# smart_water_heater_v1.net
KiCad netlist of a schematic drawn in EAGLE
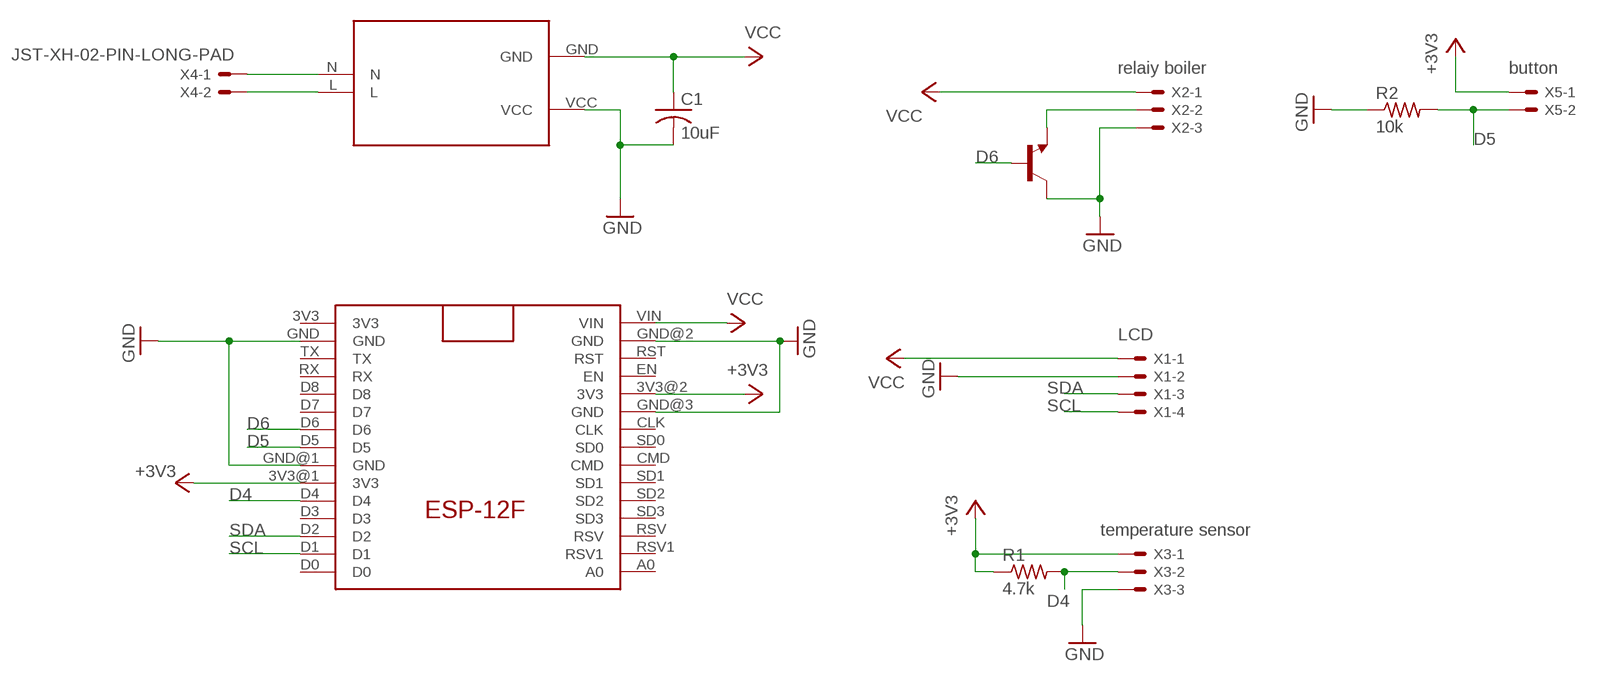
[diagram p0: schematic, sheet 1]

(export (version "E")
  (design (tool "Eeschema 10.0.6"))
  (components
    (comp (ref "C1")
      (value "10uF")
      (footprint "eagle-import:C025-025X050")
      (libsource (lib "eagle-import") (part "C-US025-025X050"))
    )
    (comp (ref "R1")
      (value "4.7k")
      (footprint "eagle-import:0204_7")
      (libsource (lib "eagle-import") (part "R-US_0204/7"))
    )
    (comp (ref "R2")
      (value "10k")
      (footprint "eagle-import:0204_7")
      (libsource (lib "eagle-import") (part "R-US_0204/7"))
    )
    (comp (ref "T1")
      (value "2N2222")
      (footprint "eagle-import:TO92-EBC-OVAL")
      (libsource (lib "eagle-import") (part "2N2222"))
    )
    (comp (ref "U$1")
      (value "ESP-12F")
      (footprint "eagle-import:ESP-12F")
      (libsource (lib "eagle-import") (part "ESP-12F"))
    )
    (comp (ref "U$2")
      (value "HLK-5M05")
      (footprint "eagle-import:CONV_HLK-5M05")
      (libsource (lib "eagle-import") (part "HLK-5M05"))
    )
    (comp (ref "X1")
      (value "22-23-2041")
      (footprint "eagle-import:22-23-2041")
      (fields (field (name "MF") "MOLEX"))
      (libsource (lib "eagle-import") (part "22-23-2041"))
    )
    (comp (ref "X2")
      (value "22-23-2031")
      (footprint "eagle-import:22-23-2031")
      (fields (field (name "MF") "MOLEX"))
      (libsource (lib "eagle-import") (part "22-23-2031"))
    )
    (comp (ref "X3")
      (value "22-23-2031")
      (footprint "eagle-import:22-23-2031")
      (fields (field (name "MF") "MOLEX"))
      (libsource (lib "eagle-import") (part "22-23-2031"))
    )
    (comp (ref "X4")
      (value "JST-XH-02-PIN-LONG-PAD")
      (footprint "eagle-import:JST-XH-02-PACKAGE-LONG-PAD")
      (libsource (lib "eagle-import") (part "JST-XH-02-PIN-LONG-PAD"))
    )
    (comp (ref "X5")
      (value "22-23-2021")
      (footprint "eagle-import:22-23-2021")
      (fields (field (name "MF") "MOLEX"))
      (libsource (lib "eagle-import") (part "22-23-2021"))
    )
  )
  (nets
    (net (code "1") (name "+3V3") (class "Default")
      (node (ref "R1") (pin "1") (pinfunction "1_1") (pintype "passive"))
      (node (ref "U$1") (pin "3V3@1") (pinfunction "3V3_3V3@1") (pintype "bidirectional"))
      (node (ref "U$1") (pin "3V3@2") (pinfunction "3V3_3V3@2") (pintype "bidirectional"))
      (node (ref "X3") (pin "1") (pinfunction "S_1") (pintype "passive"))
      (node (ref "X5") (pin "1") (pinfunction "S_1") (pintype "passive"))
    )
    (net (code "2") (name "/D4") (class "Default")
      (node (ref "R1") (pin "2") (pinfunction "2_2") (pintype "passive"))
      (node (ref "U$1") (pin "D4") (pinfunction "D4_D4") (pintype "bidirectional"))
      (node (ref "X3") (pin "2") (pinfunction "S_2") (pintype "passive"))
    )
    (net (code "3") (name "/D5") (class "Default")
      (node (ref "R2") (pin "2") (pinfunction "2_2") (pintype "passive"))
      (node (ref "U$1") (pin "D5") (pinfunction "D5_D5") (pintype "bidirectional"))
      (node (ref "X5") (pin "2") (pinfunction "S_2") (pintype "passive"))
    )
    (net (code "4") (name "/D6") (class "Default")
      (node (ref "T1") (pin "B") (pinfunction "B_B") (pintype "passive"))
      (node (ref "U$1") (pin "D6") (pinfunction "D6_D6") (pintype "bidirectional"))
    )
    (net (code "5") (name "/SCL") (class "Default")
      (node (ref "U$1") (pin "D1") (pinfunction "D1_D1") (pintype "bidirectional"))
      (node (ref "X1") (pin "4") (pinfunction "S_4") (pintype "passive"))
    )
    (net (code "6") (name "/SDA") (class "Default")
      (node (ref "U$1") (pin "D2") (pinfunction "D2_D2") (pintype "bidirectional"))
      (node (ref "X1") (pin "3") (pinfunction "S_3") (pintype "passive"))
    )
    (net (code "7") (name "GND") (class "Default")
      (node (ref "C1") (pin "2") (pinfunction "2_2") (pintype "passive"))
      (node (ref "R2") (pin "1") (pinfunction "1_1") (pintype "passive"))
      (node (ref "T1") (pin "C") (pinfunction "C_C") (pintype "passive"))
      (node (ref "U$1") (pin "GND") (pinfunction "GND_GND") (pintype "bidirectional"))
      (node (ref "U$1") (pin "GND@1") (pinfunction "GND_GND@1") (pintype "bidirectional"))
      (node (ref "U$1") (pin "GND@2") (pinfunction "GND_GND@2") (pintype "bidirectional"))
      (node (ref "U$1") (pin "GND@3") (pinfunction "GND_GND@3") (pintype "bidirectional"))
      (node (ref "U$2") (pin "VCC") (pinfunction "VCC_VCC") (pintype "bidirectional"))
      (node (ref "X1") (pin "2") (pinfunction "S_2") (pintype "passive"))
      (node (ref "X2") (pin "3") (pinfunction "S_3") (pintype "passive"))
      (node (ref "X3") (pin "3") (pinfunction "S_3") (pintype "passive"))
    )
    (net (code "8") (name "Net-(X2B-S)") (class "Default")
      (node (ref "T1") (pin "E") (pinfunction "E_E") (pintype "passive"))
      (node (ref "X2") (pin "2") (pinfunction "S_2") (pintype "passive"))
    )
    (net (code "9") (name "Net-(X4A-S)") (class "Default")
      (node (ref "U$2") (pin "N") (pinfunction "N_N") (pintype "bidirectional"))
      (node (ref "X4") (pin "1") (pinfunction "S_1") (pintype "passive"))
    )
    (net (code "10") (name "Net-(X4B-S)") (class "Default")
      (node (ref "U$2") (pin "L") (pinfunction "L_L") (pintype "bidirectional"))
      (node (ref "X4") (pin "2") (pinfunction "S_2") (pintype "passive"))
    )
    (net (code "11") (name "VCC") (class "Default")
      (node (ref "C1") (pin "1") (pinfunction "1_1") (pintype "passive"))
      (node (ref "U$1") (pin "VIN") (pinfunction "VIN_VIN") (pintype "bidirectional"))
      (node (ref "U$2") (pin "GND") (pinfunction "GND_GND") (pintype "bidirectional"))
      (node (ref "X1") (pin "1") (pinfunction "S_1") (pintype "passive"))
      (node (ref "X2") (pin "1") (pinfunction "S_1") (pintype "passive"))
    )
    (net (code "12") (name "unconnected-(U$1-Pad3V3)") (class "Default")
      (node (ref "U$1") (pin "3V3") (pinfunction "3V3_3V3") (pintype "bidirectional"))
    )
    (net (code "13") (name "unconnected-(U$1-PadA0)") (class "Default")
      (node (ref "U$1") (pin "A0") (pinfunction "A0_A0") (pintype "bidirectional"))
    )
    (net (code "14") (name "unconnected-(U$1-PadCLK)") (class "Default")
      (node (ref "U$1") (pin "CLK") (pinfunction "CLK_CLK") (pintype "bidirectional"))
    )
    (net (code "15") (name "unconnected-(U$1-PadCMD)") (class "Default")
      (node (ref "U$1") (pin "CMD") (pinfunction "CMD_CMD") (pintype "bidirectional"))
    )
    (net (code "16") (name "unconnected-(U$1-PadD0)") (class "Default")
      (node (ref "U$1") (pin "D0") (pinfunction "D0_D0") (pintype "bidirectional"))
    )
    (net (code "17") (name "unconnected-(U$1-PadD3)") (class "Default")
      (node (ref "U$1") (pin "D3") (pinfunction "D3_D3") (pintype "bidirectional"))
    )
    (net (code "18") (name "unconnected-(U$1-PadD7)") (class "Default")
      (node (ref "U$1") (pin "D7") (pinfunction "D7_D7") (pintype "bidirectional"))
    )
    (net (code "19") (name "unconnected-(U$1-PadD8)") (class "Default")
      (node (ref "U$1") (pin "D8") (pinfunction "D8_D8") (pintype "bidirectional"))
    )
    (net (code "20") (name "unconnected-(U$1-PadEN)") (class "Default")
      (node (ref "U$1") (pin "EN") (pinfunction "EN_EN") (pintype "bidirectional"))
    )
    (net (code "21") (name "unconnected-(U$1-PadRST)") (class "Default")
      (node (ref "U$1") (pin "RST") (pinfunction "RST_RST") (pintype "bidirectional"))
    )
    (net (code "22") (name "unconnected-(U$1-PadRSV)") (class "Default")
      (node (ref "U$1") (pin "RSV") (pinfunction "RSV_RSV") (pintype "bidirectional"))
    )
    (net (code "23") (name "unconnected-(U$1-PadRSV1)") (class "Default")
      (node (ref "U$1") (pin "RSV1") (pinfunction "RSV1_RSV1") (pintype "bidirectional"))
    )
    (net (code "24") (name "unconnected-(U$1-PadRX)") (class "Default")
      (node (ref "U$1") (pin "RX") (pinfunction "RX_RX") (pintype "bidirectional"))
    )
    (net (code "25") (name "unconnected-(U$1-PadSD0)") (class "Default")
      (node (ref "U$1") (pin "SD0") (pinfunction "SD0_SD0") (pintype "bidirectional"))
    )
    (net (code "26") (name "unconnected-(U$1-PadSD1)") (class "Default")
      (node (ref "U$1") (pin "SD1") (pinfunction "SD1_SD1") (pintype "bidirectional"))
    )
    (net (code "27") (name "unconnected-(U$1-PadSD2)") (class "Default")
      (node (ref "U$1") (pin "SD2") (pinfunction "SD2_SD2") (pintype "bidirectional"))
    )
    (net (code "28") (name "unconnected-(U$1-PadSD3)") (class "Default")
      (node (ref "U$1") (pin "SD3") (pinfunction "SD3_SD3") (pintype "bidirectional"))
    )
    (net (code "29") (name "unconnected-(U$1-PadTX)") (class "Default")
      (node (ref "U$1") (pin "TX") (pinfunction "TX_TX") (pintype "bidirectional"))
    )
  )
)
